# STM32F429VIT6-v1_0_0.net
KiCad netlist of a schematic drawn in EAGLE
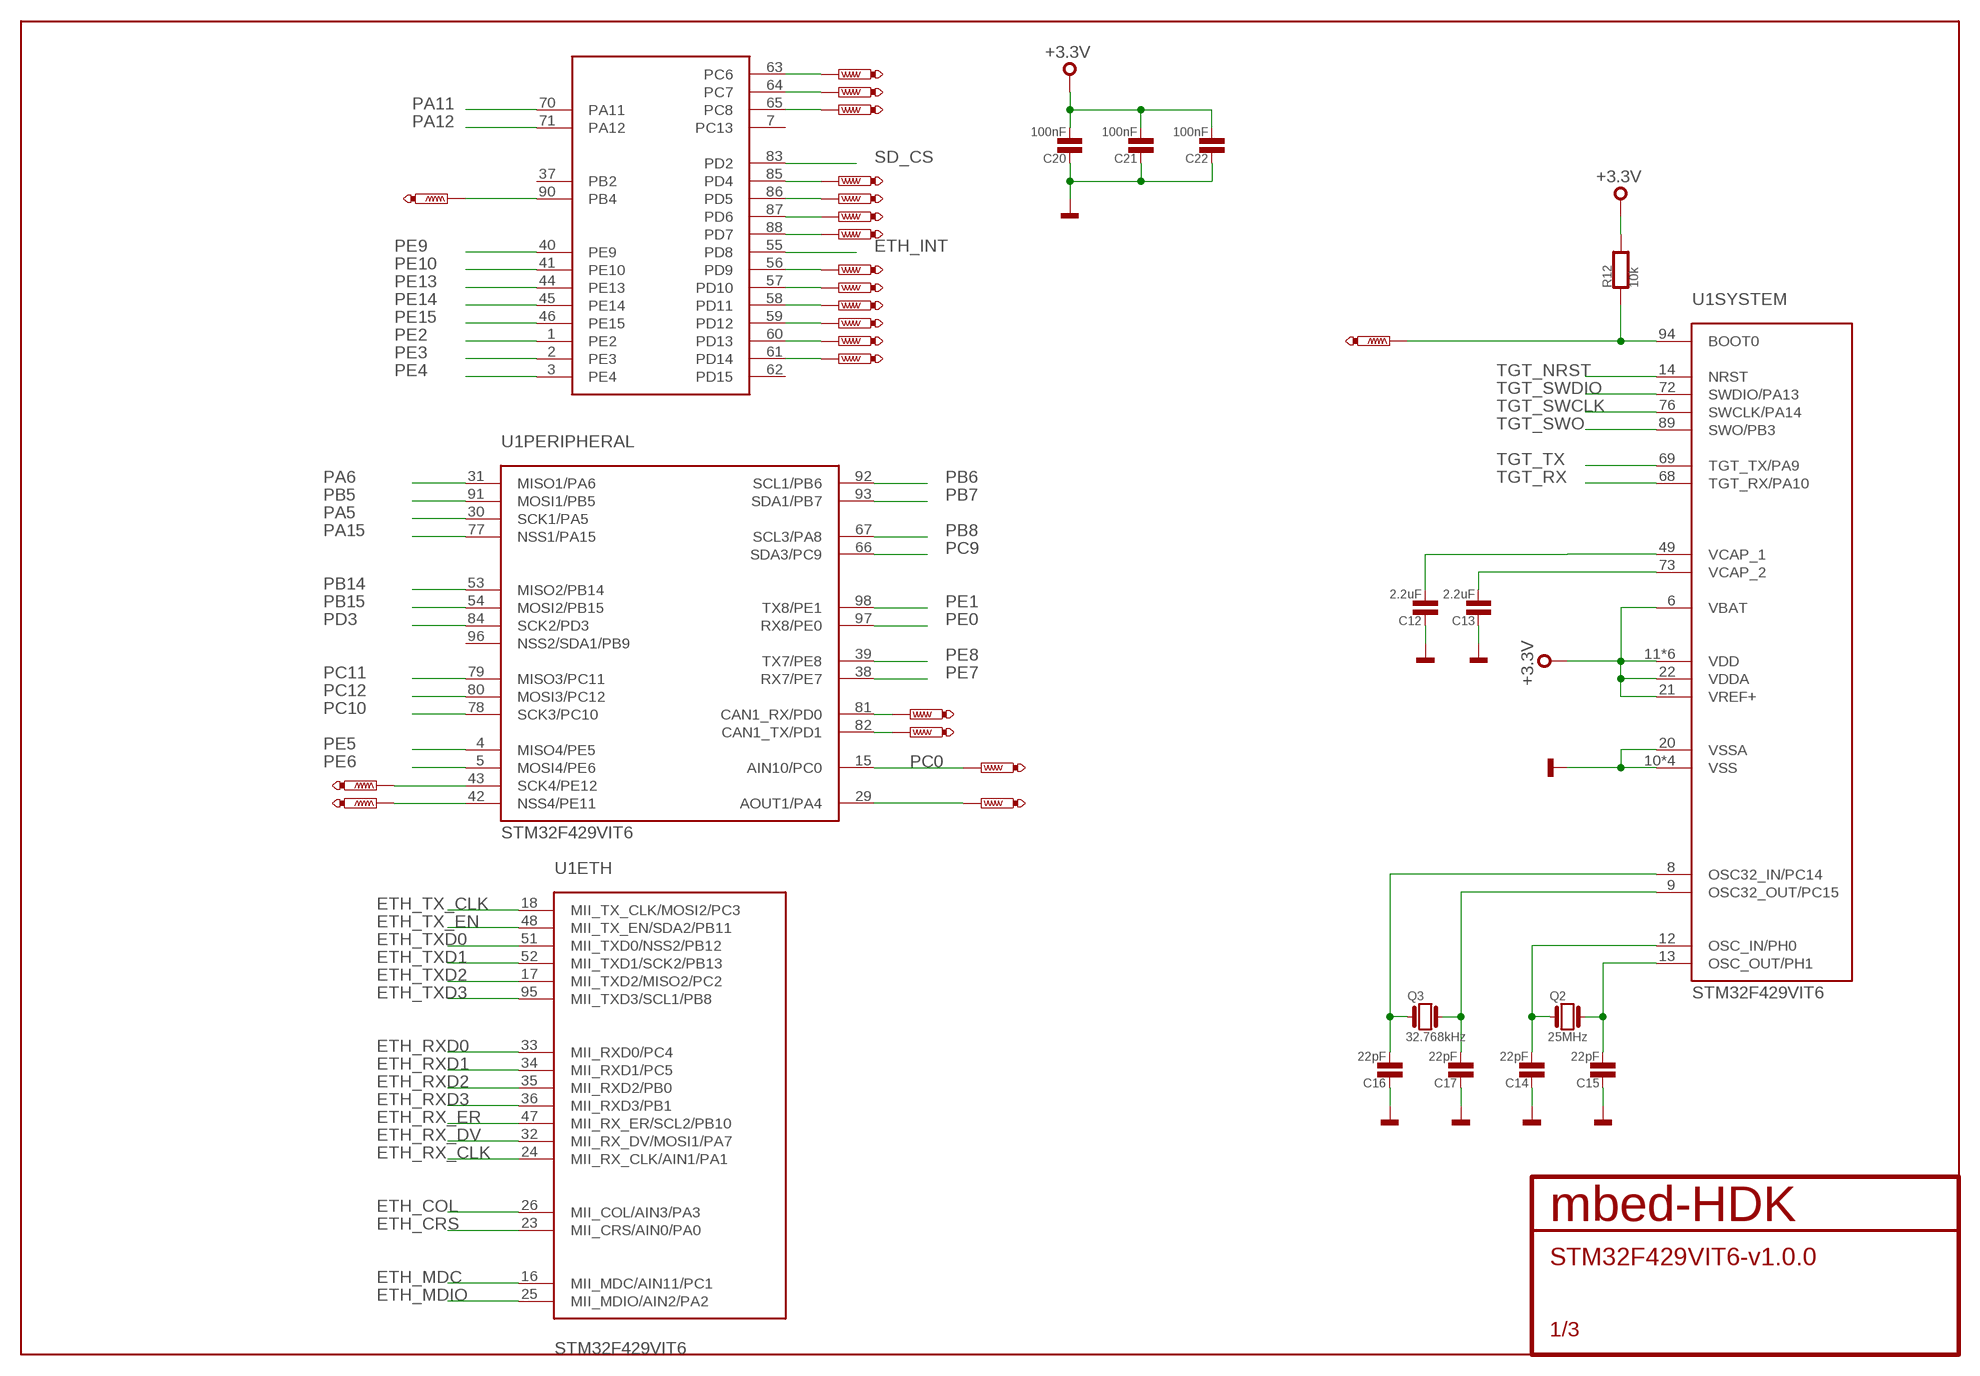
[diagram p0: schematic, sheet 1]
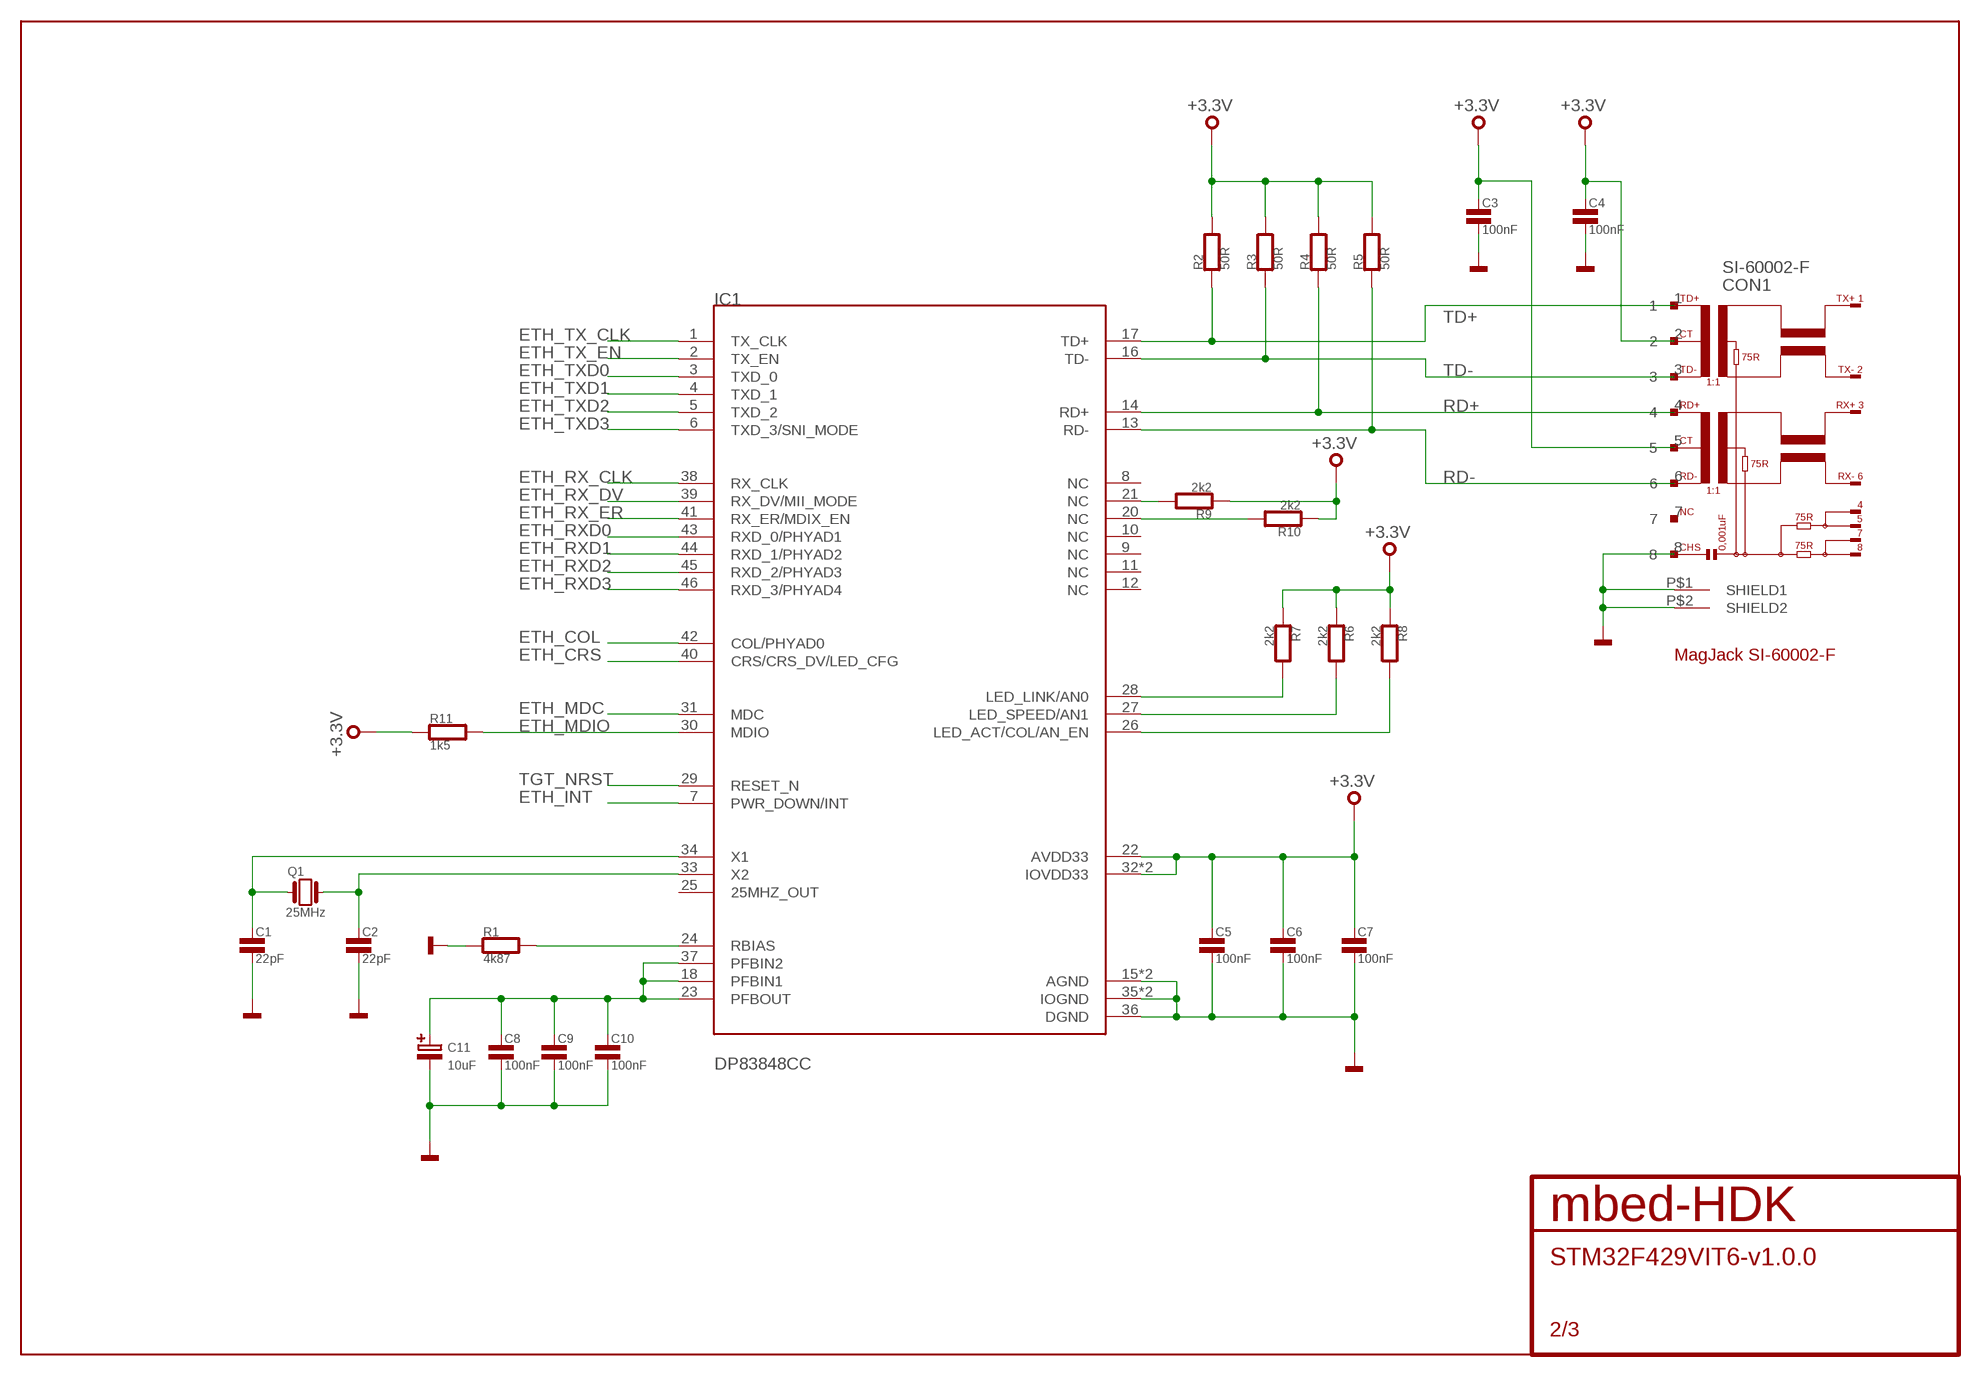
[diagram p1: schematic, sheet 2]
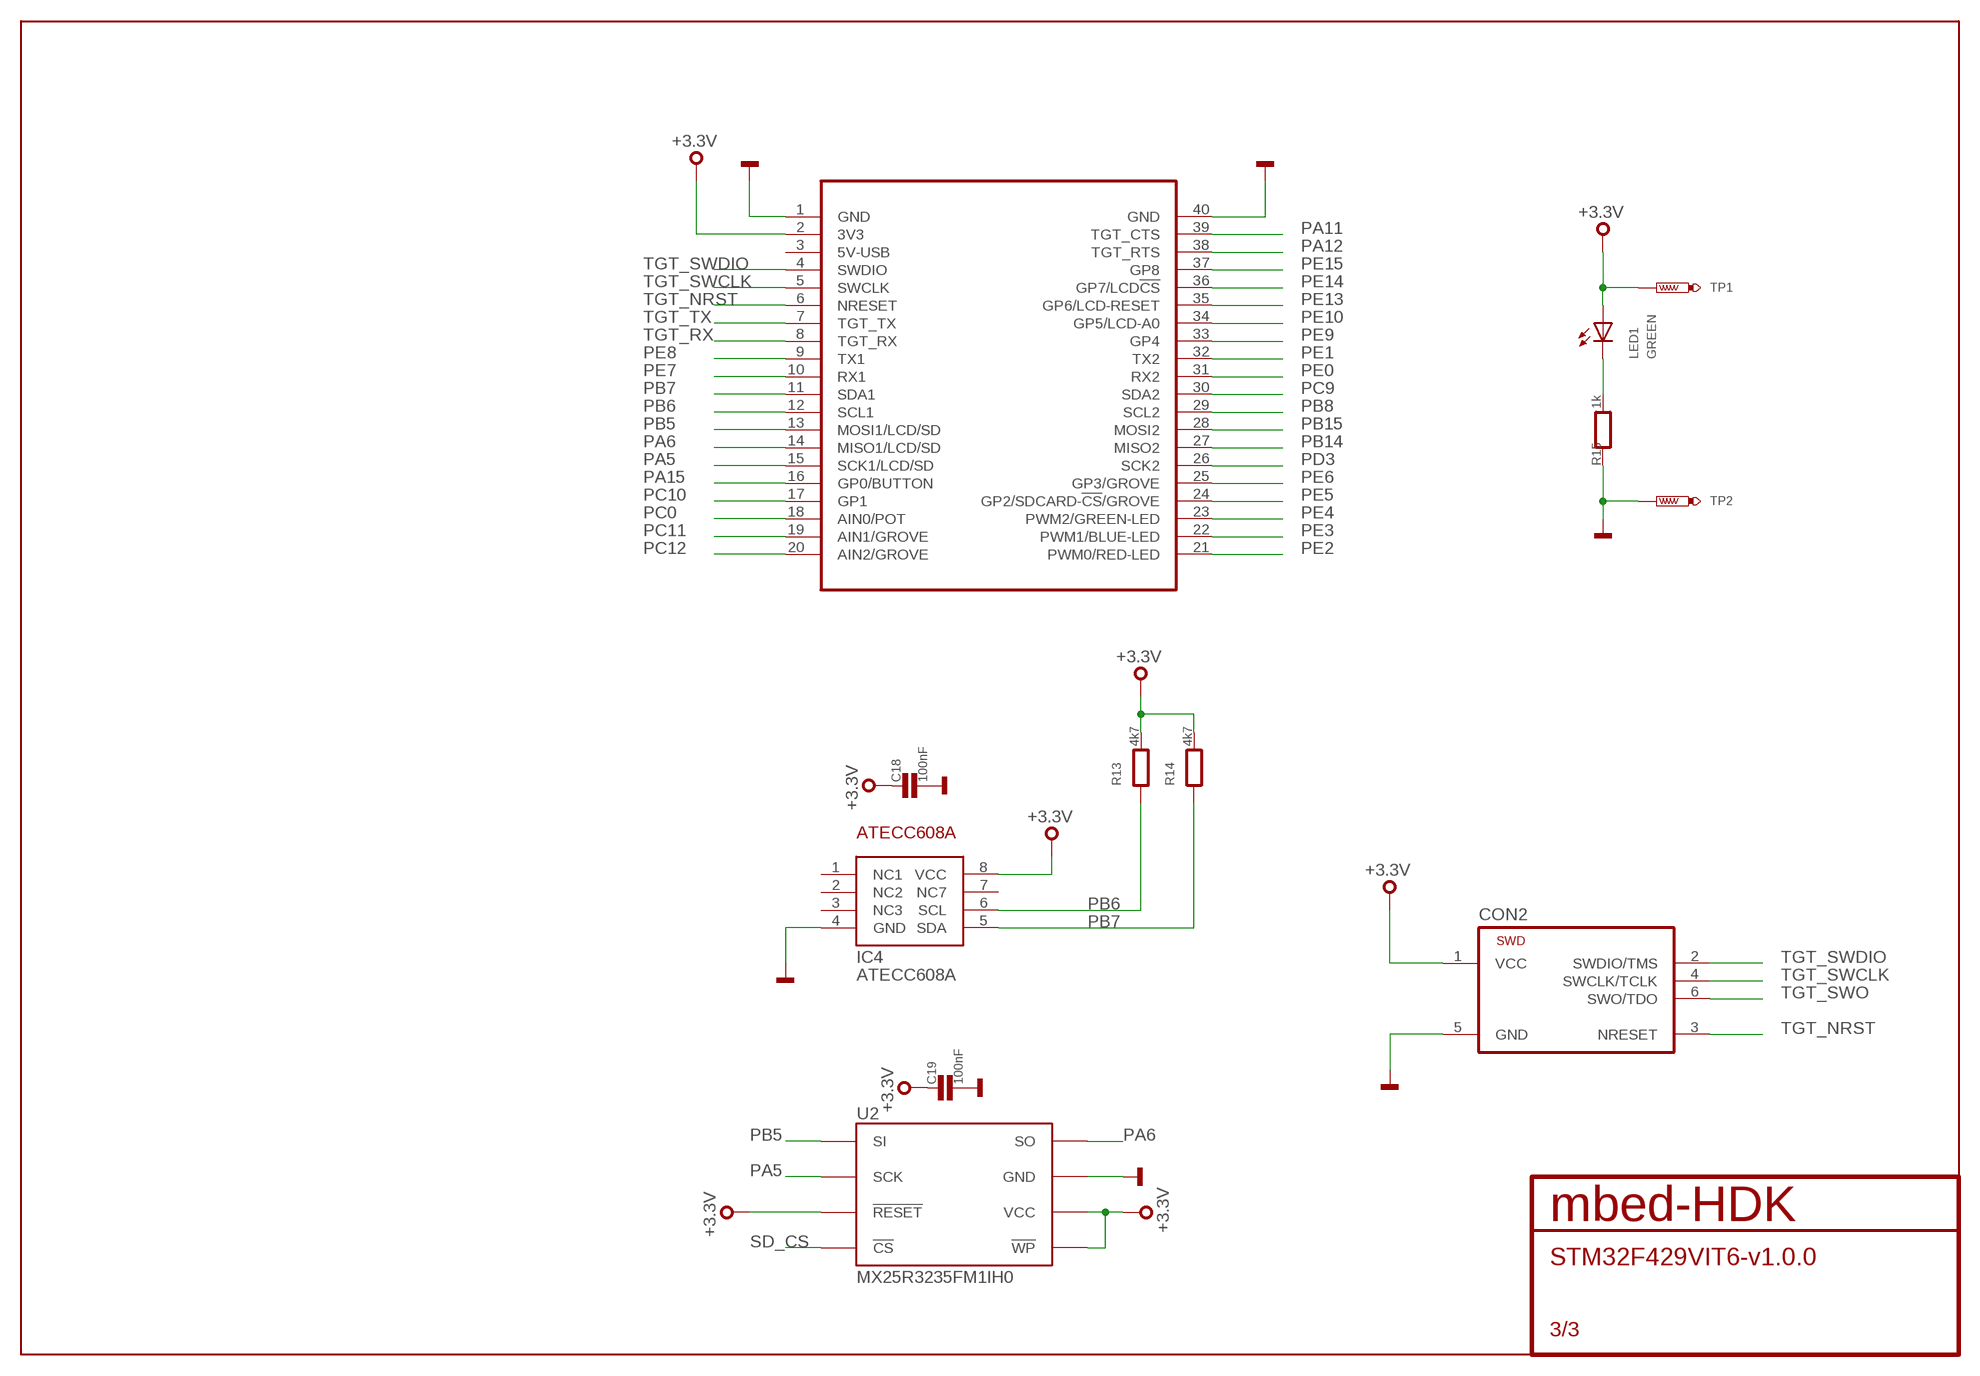
[diagram p2: schematic, sheet 3]

(export (version "E")
  (design (tool "Eeschema 10.0.6"))
  (components
    (comp (ref "C12")
      (value "2.2uF")
      (footprint "eagle-import:0402")
      (libsource (lib "eagle-import") (part "C0402"))
    )
    (comp (ref "C13")
      (value "2.2uF")
      (footprint "eagle-import:0402")
      (libsource (lib "eagle-import") (part "C0402"))
    )
    (comp (ref "C14")
      (value "22pF")
      (footprint "eagle-import:0603")
      (libsource (lib "eagle-import") (part "C0603"))
    )
    (comp (ref "C15")
      (value "22pF")
      (footprint "eagle-import:0603")
      (libsource (lib "eagle-import") (part "C0603"))
    )
    (comp (ref "C16")
      (value "22pF")
      (footprint "eagle-import:0603")
      (libsource (lib "eagle-import") (part "C0603"))
    )
    (comp (ref "C17")
      (value "22pF")
      (footprint "eagle-import:0603")
      (libsource (lib "eagle-import") (part "C0603"))
    )
    (comp (ref "C20")
      (value "100nF")
      (footprint "eagle-import:0402")
      (libsource (lib "eagle-import") (part "C0402"))
    )
    (comp (ref "C21")
      (value "100nF")
      (footprint "eagle-import:0402")
      (libsource (lib "eagle-import") (part "C0402"))
    )
    (comp (ref "C22")
      (value "100nF")
      (footprint "eagle-import:0402")
      (libsource (lib "eagle-import") (part "C0402"))
    )
    (comp (ref "Q2")
      (value "25MHz")
      (footprint "eagle-import:3.2X.2.5")
      (libsource (lib "eagle-import") (part "GENERIC-CRYSTAL_3.2X2.5"))
    )
    (comp (ref "Q3")
      (value "32.768kHz")
      (footprint "eagle-import:FC135")
      (libsource (lib "eagle-import") (part "GENERIC-CRYSTAL_FC135"))
    )
    (comp (ref "R12")
      (value "10k")
      (footprint "eagle-import:0402")
      (libsource (lib "eagle-import") (part "R0402"))
    )
    (comp (ref "TP3")
      (value "PTR1TP06R")
      (footprint "eagle-import:TP06R")
      (libsource (lib "eagle-import") (part "PTR1TP06R"))
    )
    (comp (ref "TP4")
      (value "PTR1TP06R")
      (footprint "eagle-import:TP06R")
      (libsource (lib "eagle-import") (part "PTR1TP06R"))
    )
    (comp (ref "TP5")
      (value "PTR1TP06R")
      (footprint "eagle-import:TP06R")
      (libsource (lib "eagle-import") (part "PTR1TP06R"))
    )
    (comp (ref "TP6")
      (value "PTR1TP06R")
      (footprint "eagle-import:TP06R")
      (libsource (lib "eagle-import") (part "PTR1TP06R"))
    )
    (comp (ref "TP7")
      (value "PTR1TP06R")
      (footprint "eagle-import:TP06R")
      (libsource (lib "eagle-import") (part "PTR1TP06R"))
    )
    (comp (ref "TP8")
      (value "PTR1TP06R")
      (footprint "eagle-import:TP06R")
      (libsource (lib "eagle-import") (part "PTR1TP06R"))
    )
    (comp (ref "TP9")
      (value "PTR1TP06R")
      (footprint "eagle-import:TP06R")
      (libsource (lib "eagle-import") (part "PTR1TP06R"))
    )
    (comp (ref "TP10")
      (value "PTR1TP06R")
      (footprint "eagle-import:TP06R")
      (libsource (lib "eagle-import") (part "PTR1TP06R"))
    )
    (comp (ref "TP11")
      (value "PTR1TP06R")
      (footprint "eagle-import:TP06R")
      (libsource (lib "eagle-import") (part "PTR1TP06R"))
    )
    (comp (ref "TP12")
      (value "PTR1TP06R")
      (footprint "eagle-import:TP06R")
      (libsource (lib "eagle-import") (part "PTR1TP06R"))
    )
    (comp (ref "TP13")
      (value "PTR1TP06R")
      (footprint "eagle-import:TP06R")
      (libsource (lib "eagle-import") (part "PTR1TP06R"))
    )
    (comp (ref "TP15")
      (value "PTR1TP06R")
      (footprint "eagle-import:TP06R")
      (libsource (lib "eagle-import") (part "PTR1TP06R"))
    )
    (comp (ref "TP16")
      (value "PTR1TP06R")
      (footprint "eagle-import:TP06R")
      (libsource (lib "eagle-import") (part "PTR1TP06R"))
    )
    (comp (ref "TP17")
      (value "PTR1TP06R")
      (footprint "eagle-import:TP06R")
      (libsource (lib "eagle-import") (part "PTR1TP06R"))
    )
    (comp (ref "TP18")
      (value "PTR1TP06R")
      (footprint "eagle-import:TP06R")
      (libsource (lib "eagle-import") (part "PTR1TP06R"))
    )
    (comp (ref "TP19")
      (value "PTR1TP06R")
      (footprint "eagle-import:TP06R")
      (libsource (lib "eagle-import") (part "PTR1TP06R"))
    )
    (comp (ref "TP20")
      (value "PTR1TP06R")
      (footprint "eagle-import:TP06R")
      (libsource (lib "eagle-import") (part "PTR1TP06R"))
    )
    (comp (ref "TP21")
      (value "PTR1TP06R")
      (footprint "eagle-import:TP06R")
      (libsource (lib "eagle-import") (part "PTR1TP06R"))
    )
    (comp (ref "TP22")
      (value "PTR1TP06R")
      (footprint "eagle-import:TP06R")
      (libsource (lib "eagle-import") (part "PTR1TP06R"))
    )
    (comp (ref "TP23")
      (value "PTR1TP06R")
      (footprint "eagle-import:TP06R")
      (libsource (lib "eagle-import") (part "PTR1TP06R"))
    )
    (comp (ref "TP24")
      (value "PTR1TP06R")
      (footprint "eagle-import:TP06R")
      (libsource (lib "eagle-import") (part "PTR1TP06R"))
    )
    (comp (ref "U1")
      (value "STM32F429VIT6")
      (footprint "eagle-import:QFP50P1600X1600X160-100N")
      (libsource (lib "eagle-import") (part "STM32F429VIT6"))
    )
    (comp (ref "C18")
      (value "100nF")
      (footprint "eagle-import:0402")
      (libsource (lib "eagle-import") (part "CAPACITOR0402"))
    )
    (comp (ref "C19")
      (value "100nF")
      (footprint "eagle-import:0402")
      (libsource (lib "eagle-import") (part "CAPACITOR0402"))
    )
    (comp (ref "CON2")
      (value "TC2030-CTX-NL")
      (footprint "eagle-import:TC2030-CTX-NL")
      (libsource (lib "eagle-import") (part "TC2030-CTX-NL"))
    )
    (comp (ref "IC4")
      (value "ATECC608A")
      (footprint "eagle-import:SO8")
      (libsource (lib "eagle-import") (part "ATECC608A"))
    )
    (comp (ref "LED1")
      (value "GREEN")
      (footprint "eagle-import:CHIPLED_0603")
      (fields (field (name "MF") "Wurth Electronics Inc"))
      (libsource (lib "eagle-import") (part "SMD_LED0603"))
    )
    (comp (ref "MOD1")
      (value "MODULE_DAUGHTER")
      (footprint "eagle-import:MODULE_DAUGHTER")
      (libsource (lib "eagle-import") (part "MODULE_DAUGHTER"))
    )
    (comp (ref "R13")
      (value "4k7")
      (footprint "eagle-import:0402")
      (libsource (lib "eagle-import") (part "RESISTOR0402"))
    )
    (comp (ref "R14")
      (value "4k7")
      (footprint "eagle-import:0402")
      (libsource (lib "eagle-import") (part "RESISTOR0402"))
    )
    (comp (ref "R15")
      (value "1k")
      (footprint "eagle-import:0603")
      (libsource (lib "eagle-import") (part "RESISTOR0603"))
    )
    (comp (ref "TP1")
      (value "TEST-POINT-50R-PTH")
      (footprint "eagle-import:TP50-PTH")
      (libsource (lib "eagle-import") (part "TEST-POINT-50R-PTH"))
    )
    (comp (ref "TP2")
      (value "TEST-POINT-50R-PTH")
      (footprint "eagle-import:TP50-PTH")
      (libsource (lib "eagle-import") (part "TEST-POINT-50R-PTH"))
    )
    (comp (ref "U2")
      (value "MX25R3235FM1IH0")
      (footprint "eagle-import:SO8")
      (fields (field (name "MF") "Macronix"))
      (libsource (lib "eagle-import") (part "MX25R3235FM1IH0"))
    )
    (comp (ref "C1")
      (value "22pF")
      (footprint "eagle-import:0402")
      (libsource (lib "eagle-import") (part "C0402"))
    )
    (comp (ref "C2")
      (value "22pF")
      (footprint "eagle-import:0402")
      (libsource (lib "eagle-import") (part "C0402"))
    )
    (comp (ref "C3")
      (value "100nF")
      (footprint "eagle-import:0402")
      (libsource (lib "eagle-import") (part "C0402"))
    )
    (comp (ref "C4")
      (value "100nF")
      (footprint "eagle-import:0402")
      (libsource (lib "eagle-import") (part "C0402"))
    )
    (comp (ref "C5")
      (value "100nF")
      (footprint "eagle-import:0402")
      (libsource (lib "eagle-import") (part "C0402"))
    )
    (comp (ref "C6")
      (value "100nF")
      (footprint "eagle-import:0402")
      (libsource (lib "eagle-import") (part "C0402"))
    )
    (comp (ref "C7")
      (value "100nF")
      (footprint "eagle-import:0402")
      (libsource (lib "eagle-import") (part "C0402"))
    )
    (comp (ref "C8")
      (value "100nF")
      (footprint "eagle-import:0402")
      (libsource (lib "eagle-import") (part "C0402"))
    )
    (comp (ref "C9")
      (value "100nF")
      (footprint "eagle-import:0402")
      (libsource (lib "eagle-import") (part "C0402"))
    )
    (comp (ref "C10")
      (value "100nF")
      (footprint "eagle-import:0402")
      (libsource (lib "eagle-import") (part "C0402"))
    )
    (comp (ref "C11")
      (value "10uF")
      (footprint "eagle-import:SMC_A")
      (libsource (lib "eagle-import") (part "C-POLA"))
    )
    (comp (ref "CON1")
      (value "SI-60002-F")
      (footprint "eagle-import:RJ45")
      (fields (field (name "MF") "Stewart Connector"))
      (libsource (lib "eagle-import") (part "SI-60002-F"))
    )
    (comp (ref "IC1")
      (value "DP83848CC")
      (footprint "eagle-import:LQFP-48")
      (libsource (lib "eagle-import") (part "DP83848CC"))
    )
    (comp (ref "Q1")
      (value "25MHz")
      (footprint "eagle-import:3.2X.2.5")
      (libsource (lib "eagle-import") (part "GENERIC-CRYSTAL_3.2X2.5"))
    )
    (comp (ref "R1")
      (value "4k87")
      (footprint "eagle-import:0402")
      (libsource (lib "eagle-import") (part "R0402"))
    )
    (comp (ref "R2")
      (value "50R")
      (footprint "eagle-import:0402")
      (libsource (lib "eagle-import") (part "R0402"))
    )
    (comp (ref "R3")
      (value "50R")
      (footprint "eagle-import:0402")
      (libsource (lib "eagle-import") (part "R0402"))
    )
    (comp (ref "R4")
      (value "50R")
      (footprint "eagle-import:0402")
      (libsource (lib "eagle-import") (part "R0402"))
    )
    (comp (ref "R5")
      (value "50R")
      (footprint "eagle-import:0402")
      (libsource (lib "eagle-import") (part "R0402"))
    )
    (comp (ref "R6")
      (value "2k2")
      (footprint "eagle-import:0402")
      (libsource (lib "eagle-import") (part "R0402"))
    )
    (comp (ref "R7")
      (value "2k2")
      (footprint "eagle-import:0402")
      (libsource (lib "eagle-import") (part "R0402"))
    )
    (comp (ref "R8")
      (value "2k2")
      (footprint "eagle-import:0402")
      (libsource (lib "eagle-import") (part "R0402"))
    )
    (comp (ref "R9")
      (value "2k2")
      (footprint "eagle-import:0402")
      (libsource (lib "eagle-import") (part "R0402"))
    )
    (comp (ref "R10")
      (value "2k2")
      (footprint "eagle-import:0402")
      (libsource (lib "eagle-import") (part "R0402"))
    )
    (comp (ref "R11")
      (value "1k5")
      (footprint "eagle-import:0402")
      (libsource (lib "eagle-import") (part "R0402"))
    )
  )
  (nets
    (net (code "1") (name "+3.3V") (class "Default")
      (node (ref "C18") (pin "1") (pinfunction "P$1_1") (pintype "passive"))
      (node (ref "C19") (pin "1") (pinfunction "P$1_1") (pintype "passive"))
      (node (ref "C20") (pin "2") (pinfunction "P$2_2") (pintype "passive"))
      (node (ref "C21") (pin "2") (pinfunction "P$2_2") (pintype "passive"))
      (node (ref "C22") (pin "2") (pinfunction "P$2_2") (pintype "passive"))
      (node (ref "C3") (pin "1") (pinfunction "P$1_1") (pintype "passive"))
      (node (ref "C4") (pin "1") (pinfunction "P$1_1") (pintype "passive"))
      (node (ref "C5") (pin "1") (pinfunction "P$1_1") (pintype "passive"))
      (node (ref "C6") (pin "1") (pinfunction "P$1_1") (pintype "passive"))
      (node (ref "C7") (pin "1") (pinfunction "P$1_1") (pintype "passive"))
      (node (ref "CON1") (pin "2") (pinfunction "2_2") (pintype "passive"))
      (node (ref "CON1") (pin "5") (pinfunction "5_5") (pintype "passive"))
      (node (ref "CON2") (pin "1") (pinfunction "VCC_1") (pintype "passive"))
      (node (ref "IC1") (pin "22") (pinfunction "AVDD33_22") (pintype "bidirectional"))
      (node (ref "IC1") (pin "32") (pinfunction "IOVDD33_32") (pintype "bidirectional"))
      (node (ref "IC1") (pin "48") (pinfunction "IOVDD33_48") (pintype "bidirectional"))
      (node (ref "IC4") (pin "8") (pinfunction "VCC_8") (pintype "bidirectional"))
      (node (ref "LED1") (pin "A") (pinfunction "A_A") (pintype "passive"))
      (node (ref "MOD1") (pin "2") (pinfunction "3V3_2") (pintype "bidirectional"))
      (node (ref "R10") (pin "1") (pinfunction "P$1_1") (pintype "passive"))
      (node (ref "R11") (pin "1") (pinfunction "P$1_1") (pintype "passive"))
      (node (ref "R12") (pin "2") (pinfunction "P$2_2") (pintype "passive"))
      (node (ref "R13") (pin "2") (pinfunction "P$2_2") (pintype "passive"))
      (node (ref "R14") (pin "2") (pinfunction "P$2_2") (pintype "passive"))
      (node (ref "R2") (pin "2") (pinfunction "P$2_2") (pintype "passive"))
      (node (ref "R3") (pin "2") (pinfunction "P$2_2") (pintype "passive"))
      (node (ref "R4") (pin "2") (pinfunction "P$2_2") (pintype "passive"))
      (node (ref "R5") (pin "2") (pinfunction "P$2_2") (pintype "passive"))
      (node (ref "R6") (pin "1") (pinfunction "P$1_1") (pintype "passive"))
      (node (ref "R7") (pin "1") (pinfunction "P$1_1") (pintype "passive"))
      (node (ref "R8") (pin "1") (pinfunction "P$1_1") (pintype "passive"))
      (node (ref "R9") (pin "1") (pinfunction "P$1_1") (pintype "passive"))
      (node (ref "TP1") (pin "TP") (pinfunction "TP_TP") (pintype "input"))
      (node (ref "U1") (pin "100") (pinfunction "VDD_100") (pintype "power_in"))
      (node (ref "U1") (pin "11") (pinfunction "VDD_11") (pintype "power_in"))
      (node (ref "U1") (pin "19") (pinfunction "VDD_19") (pintype "power_in"))
      (node (ref "U1") (pin "21") (pinfunction "VREF+_21") (pintype "power_in"))
      (node (ref "U1") (pin "22") (pinfunction "VDDA_22") (pintype "power_in"))
      (node (ref "U1") (pin "28") (pinfunction "VDD_28") (pintype "power_in"))
      (node (ref "U1") (pin "50") (pinfunction "VDD_50") (pintype "power_in"))
      (node (ref "U1") (pin "6") (pinfunction "VBAT_6") (pintype "power_in"))
      (node (ref "U1") (pin "75") (pinfunction "VDD_75") (pintype "power_in"))
      (node (ref "U2") (pin "3") (pinfunction "~{WP}_3") (pintype "bidirectional"))
      (node (ref "U2") (pin "7") (pinfunction "~{RESET}_7") (pintype "bidirectional"))
      (node (ref "U2") (pin "8") (pinfunction "VCC_8") (pintype "bidirectional"))
    )
    (net (code "2") (name "ETH_COL") (class "Default")
      (node (ref "IC1") (pin "42") (pinfunction "COL/PHYAD0_42") (pintype "bidirectional"))
      (node (ref "U1") (pin "26") (pinfunction "MII_COL/AIN3/PA3_26") (pintype "bidirectional"))
    )
    (net (code "3") (name "ETH_CRS") (class "Default")
      (node (ref "IC1") (pin "40") (pinfunction "CRS/CRS_DV/LED_CFG_40") (pintype "bidirectional"))
      (node (ref "U1") (pin "23") (pinfunction "MII_CRS/AIN0/PA0_23") (pintype "bidirectional"))
    )
    (net (code "4") (name "ETH_INT") (class "Default")
      (node (ref "IC1") (pin "7") (pinfunction "PWR_DOWN/INT_7") (pintype "bidirectional"))
      (node (ref "U1") (pin "55") (pinfunction "PD8_55") (pintype "bidirectional"))
    )
    (net (code "5") (name "ETH_MDC") (class "Default")
      (node (ref "IC1") (pin "31") (pinfunction "MDC_31") (pintype "bidirectional"))
      (node (ref "U1") (pin "16") (pinfunction "MII_MDC/AIN11/PC1_16") (pintype "bidirectional"))
    )
    (net (code "6") (name "ETH_MDIO") (class "Default")
      (node (ref "IC1") (pin "30") (pinfunction "MDIO_30") (pintype "bidirectional"))
      (node (ref "R11") (pin "2") (pinfunction "P$2_2") (pintype "passive"))
      (node (ref "U1") (pin "25") (pinfunction "MII_MDIO/AIN2/PA2_25") (pintype "bidirectional"))
    )
    (net (code "7") (name "ETH_RXD0") (class "Default")
      (node (ref "IC1") (pin "43") (pinfunction "RXD_0/PHYAD1_43") (pintype "bidirectional"))
      (node (ref "U1") (pin "33") (pinfunction "MII_RXD0/PC4_33") (pintype "bidirectional"))
    )
    (net (code "8") (name "ETH_RXD1") (class "Default")
      (node (ref "IC1") (pin "44") (pinfunction "RXD_1/PHYAD2_44") (pintype "bidirectional"))
      (node (ref "U1") (pin "34") (pinfunction "MII_RXD1/PC5_34") (pintype "bidirectional"))
    )
    (net (code "9") (name "ETH_RXD2") (class "Default")
      (node (ref "IC1") (pin "45") (pinfunction "RXD_2/PHYAD3_45") (pintype "bidirectional"))
      (node (ref "U1") (pin "35") (pinfunction "MII_RXD2/PB0_35") (pintype "bidirectional"))
    )
    (net (code "10") (name "ETH_RXD3") (class "Default")
      (node (ref "IC1") (pin "46") (pinfunction "RXD_3/PHYAD4_46") (pintype "bidirectional"))
      (node (ref "U1") (pin "36") (pinfunction "MII_RXD3/PB1_36") (pintype "bidirectional"))
    )
    (net (code "11") (name "ETH_RX_CLK") (class "Default")
      (node (ref "IC1") (pin "38") (pinfunction "RX_CLK_38") (pintype "bidirectional"))
      (node (ref "U1") (pin "24") (pinfunction "MII_RX_CLK/AIN1/PA1_24") (pintype "bidirectional"))
    )
    (net (code "12") (name "ETH_RX_DV") (class "Default")
      (node (ref "IC1") (pin "39") (pinfunction "RX_DV/MII_MODE_39") (pintype "bidirectional"))
      (node (ref "U1") (pin "32") (pinfunction "MII_RX_DV/MOSI1/PA7_32") (pintype "bidirectional"))
    )
    (net (code "13") (name "ETH_RX_ER") (class "Default")
      (node (ref "IC1") (pin "41") (pinfunction "RX_ER/MDIX_EN_41") (pintype "bidirectional"))
      (node (ref "U1") (pin "47") (pinfunction "MII_RX_ER/SCL2/PB10_47") (pintype "bidirectional"))
    )
    (net (code "14") (name "ETH_TXD0") (class "Default")
      (node (ref "IC1") (pin "3") (pinfunction "TXD_0_3") (pintype "bidirectional"))
      (node (ref "U1") (pin "51") (pinfunction "MII_TXD0/NSS2/PB12_51") (pintype "bidirectional"))
    )
    (net (code "15") (name "ETH_TXD1") (class "Default")
      (node (ref "IC1") (pin "4") (pinfunction "TXD_1_4") (pintype "bidirectional"))
      (node (ref "U1") (pin "52") (pinfunction "MII_TXD1/SCK2/PB13_52") (pintype "bidirectional"))
    )
    (net (code "16") (name "ETH_TXD2") (class "Default")
      (node (ref "IC1") (pin "5") (pinfunction "TXD_2_5") (pintype "bidirectional"))
      (node (ref "U1") (pin "17") (pinfunction "MII_TXD2/MISO2/PC2_17") (pintype "bidirectional"))
    )
    (net (code "17") (name "ETH_TXD3") (class "Default")
      (node (ref "IC1") (pin "6") (pinfunction "TXD_3/SNI_MODE_6") (pintype "bidirectional"))
      (node (ref "U1") (pin "95") (pinfunction "MII_TXD3/SCL1/PB8_95") (pintype "bidirectional"))
    )
    (net (code "18") (name "ETH_TX_CLK") (class "Default")
      (node (ref "IC1") (pin "1") (pinfunction "TX_CLK_1") (pintype "bidirectional"))
      (node (ref "U1") (pin "18") (pinfunction "MII_TX_CLK/MOSI2/PC3_18") (pintype "bidirectional"))
    )
    (net (code "19") (name "ETH_TX_EN") (class "Default")
      (node (ref "IC1") (pin "2") (pinfunction "TX_EN_2") (pintype "bidirectional"))
      (node (ref "U1") (pin "48") (pinfunction "MII_TX_EN/SDA2/PB11_48") (pintype "bidirectional"))
    )
    (net (code "20") (name "GND") (class "Default")
      (node (ref "C1") (pin "2") (pinfunction "P$2_2") (pintype "passive"))
      (node (ref "C10") (pin "2") (pinfunction "P$2_2") (pintype "passive"))
      (node (ref "C11") (pin "-") (pinfunction "-_-") (pintype "passive"))
      (node (ref "C12") (pin "1") (pinfunction "P$1_1") (pintype "passive"))
      (node (ref "C13") (pin "1") (pinfunction "P$1_1") (pintype "passive"))
      (node (ref "C14") (pin "1") (pinfunction "P$1_1") (pintype "passive"))
      (node (ref "C15") (pin "1") (pinfunction "P$1_1") (pintype "passive"))
      (node (ref "C16") (pin "1") (pinfunction "P$1_1") (pintype "passive"))
      (node (ref "C17") (pin "1") (pinfunction "P$1_1") (pintype "passive"))
      (node (ref "C18") (pin "2") (pinfunction "P$2_2") (pintype "passive"))
      (node (ref "C19") (pin "2") (pinfunction "P$2_2") (pintype "passive"))
      (node (ref "C2") (pin "2") (pinfunction "P$2_2") (pintype "passive"))
      (node (ref "C20") (pin "1") (pinfunction "P$1_1") (pintype "passive"))
      (node (ref "C21") (pin "1") (pinfunction "P$1_1") (pintype "passive"))
      (node (ref "C22") (pin "1") (pinfunction "P$1_1") (pintype "passive"))
      (node (ref "C3") (pin "2") (pinfunction "P$2_2") (pintype "passive"))
      (node (ref "C4") (pin "2") (pinfunction "P$2_2") (pintype "passive"))
      (node (ref "C5") (pin "2") (pinfunction "P$2_2") (pintype "passive"))
      (node (ref "C6") (pin "2") (pinfunction "P$2_2") (pintype "passive"))
      (node (ref "C7") (pin "2") (pinfunction "P$2_2") (pintype "passive"))
      (node (ref "C8") (pin "2") (pinfunction "P$2_2") (pintype "passive"))
      (node (ref "C9") (pin "2") (pinfunction "P$2_2") (pintype "passive"))
      (node (ref "CON1") (pin "8") (pinfunction "8_8") (pintype "passive"))
      (node (ref "CON1") (pin "P$1") (pinfunction "SHIELD1_P$1") (pintype "bidirectional"))
      (node (ref "CON1") (pin "P$2") (pinfunction "SHIELD2_P$2") (pintype "bidirectional"))
      (node (ref "CON2") (pin "5") (pinfunction "GND_5") (pintype "passive"))
      (node (ref "IC1") (pin "15") (pinfunction "AGND_15") (pintype "bidirectional"))
      (node (ref "IC1") (pin "19") (pinfunction "AGND_19") (pintype "bidirectional"))
      (node (ref "IC1") (pin "35") (pinfunction "IOGND_35") (pintype "bidirectional"))
      (node (ref "IC1") (pin "36") (pinfunction "DGND_36") (pintype "bidirectional"))
      (node (ref "IC1") (pin "47") (pinfunction "IOGND_47") (pintype "bidirectional"))
      (node (ref "IC4") (pin "4") (pinfunction "GND_4") (pintype "bidirectional"))
      (node (ref "MOD1") (pin "1") (pinfunction "GND_1") (pintype "bidirectional"))
      (node (ref "MOD1") (pin "40") (pinfunction "GND_40") (pintype "bidirectional"))
      (node (ref "R1") (pin "1") (pinfunction "P$1_1") (pintype "passive"))
      (node (ref "R15") (pin "1") (pinfunction "P$1_1") (pintype "passive"))
      (node (ref "TP2") (pin "TP") (pinfunction "TP_TP") (pintype "input"))
      (node (ref "U1") (pin "10") (pinfunction "VSS_10") (pintype "power_in"))
      (node (ref "U1") (pin "20") (pinfunction "VSSA_20") (pintype "power_in"))
      (node (ref "U1") (pin "27") (pinfunction "VSS_27") (pintype "power_in"))
      (node (ref "U1") (pin "74") (pinfunction "VSS_74") (pintype "power_in"))
      (node (ref "U1") (pin "99") (pinfunction "VSS_99") (pintype "power_in"))
      (node (ref "U2") (pin "4") (pinfunction "GND_4") (pintype "bidirectional"))
    )
    (net (code "21") (name "Net-(C1-P$1)") (class "Default")
      (node (ref "C1") (pin "1") (pinfunction "P$1_1") (pintype "passive"))
      (node (ref "IC1") (pin "34") (pinfunction "X1_34") (pintype "bidirectional"))
      (node (ref "Q1") (pin "P$1") (pinfunction "1_P$1") (pintype "passive"))
    )
    (net (code "22") (name "Net-(C2-P$1)") (class "Default")
      (node (ref "C2") (pin "1") (pinfunction "P$1_1") (pintype "passive"))
      (node (ref "IC1") (pin "33") (pinfunction "X2_33") (pintype "bidirectional"))
      (node (ref "Q1") (pin "P$3") (pinfunction "2_P$3") (pintype "passive"))
    )
    (net (code "23") (name "Net-(C10-P$1)") (class "Default")
      (node (ref "C10") (pin "1") (pinfunction "P$1_1") (pintype "passive"))
      (node (ref "C11") (pin "+") (pinfunction "+_+") (pintype "passive"))
      (node (ref "C8") (pin "1") (pinfunction "P$1_1") (pintype "passive"))
      (node (ref "C9") (pin "1") (pinfunction "P$1_1") (pintype "passive"))
      (node (ref "IC1") (pin "18") (pinfunction "PFBIN1_18") (pintype "bidirectional"))
      (node (ref "IC1") (pin "23") (pinfunction "PFBOUT_23") (pintype "bidirectional"))
      (node (ref "IC1") (pin "37") (pinfunction "PFBIN2_37") (pintype "bidirectional"))
    )
    (net (code "24") (name "Net-(C12-P$2)") (class "Default")
      (node (ref "C12") (pin "2") (pinfunction "P$2_2") (pintype "passive"))
      (node (ref "U1") (pin "49") (pinfunction "VCAP_1_49") (pintype "power_in"))
    )
    (net (code "25") (name "Net-(C13-P$2)") (class "Default")
      (node (ref "C13") (pin "2") (pinfunction "P$2_2") (pintype "passive"))
      (node (ref "U1") (pin "73") (pinfunction "VCAP_2_73") (pintype "power_in"))
    )
    (net (code "26") (name "Net-(C14-P$2)") (class "Default")
      (node (ref "C14") (pin "2") (pinfunction "P$2_2") (pintype "passive"))
      (node (ref "Q2") (pin "P$1") (pinfunction "1_P$1") (pintype "passive"))
      (node (ref "U1") (pin "12") (pinfunction "OSC_IN/PH0_12") (pintype "bidirectional"))
    )
    (net (code "27") (name "Net-(C15-P$2)") (class "Default")
      (node (ref "C15") (pin "2") (pinfunction "P$2_2") (pintype "passive"))
      (node (ref "Q2") (pin "P$3") (pinfunction "2_P$3") (pintype "passive"))
      (node (ref "U1") (pin "13") (pinfunction "OSC_OUT/PH1_13") (pintype "bidirectional"))
    )
    (net (code "28") (name "Net-(C16-P$2)") (class "Default")
      (node (ref "C16") (pin "2") (pinfunction "P$2_2") (pintype "passive"))
      (node (ref "Q3") (pin "X1") (pinfunction "1_X1") (pintype "passive"))
      (node (ref "U1") (pin "8") (pinfunction "OSC32_IN/PC14_8") (pintype "bidirectional"))
    )
    (net (code "29") (name "Net-(C17-P$2)") (class "Default")
      (node (ref "C17") (pin "2") (pinfunction "P$2_2") (pintype "passive"))
      (node (ref "Q3") (pin "X2") (pinfunction "2_X2") (pintype "passive"))
      (node (ref "U1") (pin "9") (pinfunction "OSC32_OUT/PC15_9") (pintype "bidirectional"))
    )
    (net (code "30") (name "Net-(IC1-LED_ACT{slash}COL{slash}AN_EN)") (class "Default")
      (node (ref "IC1") (pin "26") (pinfunction "LED_ACT/COL/AN_EN_26") (pintype "bidirectional"))
      (node (ref "R8") (pin "2") (pinfunction "P$2_2") (pintype "passive"))
    )
    (net (code "31") (name "Net-(IC1-LED_LINK{slash}AN0)") (class "Default")
      (node (ref "IC1") (pin "28") (pinfunction "LED_LINK/AN0_28") (pintype "bidirectional"))
      (node (ref "R7") (pin "2") (pinfunction "P$2_2") (pintype "passive"))
    )
    (net (code "32") (name "Net-(IC1-LED_SPEED{slash}AN1)") (class "Default")
      (node (ref "IC1") (pin "27") (pinfunction "LED_SPEED/AN1_27") (pintype "bidirectional"))
      (node (ref "R6") (pin "2") (pinfunction "P$2_2") (pintype "passive"))
    )
    (net (code "33") (name "Net-(IC1-RBIAS)") (class "Default")
      (node (ref "IC1") (pin "24") (pinfunction "RBIAS_24") (pintype "bidirectional"))
      (node (ref "R1") (pin "2") (pinfunction "P$2_2") (pintype "passive"))
    )
    (net (code "34") (name "Net-(R9-P$2)") (class "Default")
      (node (ref "IC1") (pin "21") (pinfunction "NC_21") (pintype "bidirectional"))
      (node (ref "R9") (pin "2") (pinfunction "P$2_2") (pintype "passive"))
    )
    (net (code "35") (name "Net-(R10-P$2)") (class "Default")
      (node (ref "IC1") (pin "20") (pinfunction "NC_20") (pintype "bidirectional"))
      (node (ref "R10") (pin "2") (pinfunction "P$2_2") (pintype "passive"))
    )
    (net (code "36") (name "Net-(R12-P$1)") (class "Default")
      (node (ref "R12") (pin "1") (pinfunction "P$1_1") (pintype "passive"))
      (node (ref "TP6") (pin "TP") (pinfunction "TP_TP") (pintype "input"))
      (node (ref "U1") (pin "94") (pinfunction "BOOT0_94") (pintype "input"))
    )
    (net (code "37") (name "Net-(R15-P$2)") (class "Default")
      (node (ref "LED1") (pin "C") (pinfunction "C_C") (pintype "passive"))
      (node (ref "R15") (pin "2") (pinfunction "P$2_2") (pintype "passive"))
    )
    (net (code "38") (name "Net-(U1B-PB4)") (class "Default")
      (node (ref "TP11") (pin "TP") (pinfunction "TP_TP") (pintype "input"))
      (node (ref "U1") (pin "90") (pinfunction "PB4_90") (pintype "bidirectional"))
    )
    (net (code "39") (name "Net-(U1B-PC6)") (class "Default")
      (node (ref "TP15") (pin "TP") (pinfunction "TP_TP") (pintype "input"))
      (node (ref "U1") (pin "63") (pinfunction "PC6_63") (pintype "bidirectional"))
    )
    (net (code "40") (name "Net-(U1B-PC7)") (class "Default")
      (node (ref "TP16") (pin "TP") (pinfunction "TP_TP") (pintype "input"))
      (node (ref "U1") (pin "64") (pinfunction "PC7_64") (pintype "bidirectional"))
    )
    (net (code "41") (name "Net-(U1B-PC8)") (class "Default")
      (node (ref "TP17") (pin "TP") (pinfunction "TP_TP") (pintype "input"))
      (node (ref "U1") (pin "65") (pinfunction "PC8_65") (pintype "bidirectional"))
    )
    (net (code "42") (name "Net-(U1B-PD4)") (class "Default")
      (node (ref "TP21") (pin "TP") (pinfunction "TP_TP") (pintype "input"))
      (node (ref "U1") (pin "85") (pinfunction "PD4_85") (pintype "bidirectional"))
    )
    (net (code "43") (name "Net-(U1B-PD5)") (class "Default")
      (node (ref "TP20") (pin "TP") (pinfunction "TP_TP") (pintype "input"))
      (node (ref "U1") (pin "86") (pinfunction "PD5_86") (pintype "bidirectional"))
    )
    (net (code "44") (name "Net-(U1B-PD6)") (class "Default")
      (node (ref "TP19") (pin "TP") (pinfunction "TP_TP") (pintype "input"))
      (node (ref "U1") (pin "87") (pinfunction "PD6_87") (pintype "bidirectional"))
    )
    (net (code "45") (name "Net-(U1B-PD7)") (class "Default")
      (node (ref "TP18") (pin "TP") (pinfunction "TP_TP") (pintype "input"))
      (node (ref "U1") (pin "88") (pinfunction "PD7_88") (pintype "bidirectional"))
    )
    (net (code "46") (name "Net-(U1B-PD9)") (class "Default")
      (node (ref "TP13") (pin "TP") (pinfunction "TP_TP") (pintype "input"))
      (node (ref "U1") (pin "56") (pinfunction "PD9_56") (pintype "bidirectional"))
    )
    (net (code "47") (name "Net-(U1B-PD10)") (class "Default")
      (node (ref "TP10") (pin "TP") (pinfunction "TP_TP") (pintype "input"))
      (node (ref "U1") (pin "57") (pinfunction "PD10_57") (pintype "bidirectional"))
    )
    (net (code "48") (name "Net-(U1B-PD11)") (class "Default")
      (node (ref "TP22") (pin "TP") (pinfunction "TP_TP") (pintype "input"))
      (node (ref "U1") (pin "58") (pinfunction "PD11_58") (pintype "bidirectional"))
    )
    (net (code "49") (name "Net-(U1B-PD12)") (class "Default")
      (node (ref "TP23") (pin "TP") (pinfunction "TP_TP") (pintype "input"))
      (node (ref "U1") (pin "59") (pinfunction "PD12_59") (pintype "bidirectional"))
    )
    (net (code "50") (name "Net-(U1B-PD13)") (class "Default")
      (node (ref "TP12") (pin "TP") (pinfunction "TP_TP") (pintype "input"))
      (node (ref "U1") (pin "60") (pinfunction "PD13_60") (pintype "bidirectional"))
    )
    (net (code "51") (name "Net-(U1B-PD14)") (class "Default")
      (node (ref "TP24") (pin "TP") (pinfunction "TP_TP") (pintype "input"))
      (node (ref "U1") (pin "61") (pinfunction "PD14_61") (pintype "bidirectional"))
    )
    (net (code "52") (name "Net-(U1C-AOUT1{slash}PA4)") (class "Default")
      (node (ref "TP7") (pin "TP") (pinfunction "TP_TP") (pintype "input"))
      (node (ref "U1") (pin "29") (pinfunction "AOUT1/PA4_29") (pintype "bidirectional"))
    )
    (net (code "53") (name "Net-(U1C-CAN1_RX{slash}PD0)") (class "Default")
      (node (ref "TP3") (pin "TP") (pinfunction "TP_TP") (pintype "input"))
      (node (ref "U1") (pin "81") (pinfunction "CAN1_RX/PD0_81") (pintype "bidirectional"))
    )
    (net (code "54") (name "Net-(U1C-CAN1_TX{slash}PD1)") (class "Default")
      (node (ref "TP4") (pin "TP") (pinfunction "TP_TP") (pintype "input"))
      (node (ref "U1") (pin "82") (pinfunction "CAN1_TX/PD1_82") (pintype "bidirectional"))
    )
    (net (code "55") (name "Net-(U1C-NSS4{slash}PE11)") (class "Default")
      (node (ref "TP8") (pin "TP") (pinfunction "TP_TP") (pintype "input"))
      (node (ref "U1") (pin "42") (pinfunction "NSS4/PE11_42") (pintype "bidirectional"))
    )
    (net (code "56") (name "Net-(U1C-SCK4{slash}PE12)") (class "Default")
      (node (ref "TP9") (pin "TP") (pinfunction "TP_TP") (pintype "input"))
      (node (ref "U1") (pin "43") (pinfunction "SCK4/PE12_43") (pintype "bidirectional"))
    )
    (net (code "57") (name "PA5") (class "Default")
      (node (ref "MOD1") (pin "15") (pinfunction "SCK1/LCD/SD_15") (pintype "bidirectional"))
      (node (ref "U1") (pin "30") (pinfunction "SCK1/PA5_30") (pintype "bidirectional"))
      (node (ref "U2") (pin "6") (pinfunction "SCK_6") (pintype "bidirectional"))
    )
    (net (code "58") (name "PA6") (class "Default")
      (node (ref "MOD1") (pin "14") (pinfunction "MISO1/LCD/SD_14") (pintype "bidirectional"))
      (node (ref "U1") (pin "31") (pinfunction "MISO1/PA6_31") (pintype "bidirectional"))
      (node (ref "U2") (pin "2") (pinfunction "SO_2") (pintype "bidirectional"))
    )
    (net (code "59") (name "PA11") (class "Default")
      (node (ref "MOD1") (pin "39") (pinfunction "TGT_CTS_39") (pintype "bidirectional"))
      (node (ref "U1") (pin "70") (pinfunction "PA11_70") (pintype "bidirectional"))
    )
    (net (code "60") (name "PA12") (class "Default")
      (node (ref "MOD1") (pin "38") (pinfunction "TGT_RTS_38") (pintype "bidirectional"))
      (node (ref "U1") (pin "71") (pinfunction "PA12_71") (pintype "bidirectional"))
    )
    (net (code "61") (name "PA15") (class "Default")
      (node (ref "MOD1") (pin "16") (pinfunction "GP0/BUTTON_16") (pintype "bidirectional"))
      (node (ref "U1") (pin "77") (pinfunction "NSS1/PA15_77") (pintype "bidirectional"))
    )
    (net (code "62") (name "PB5") (class "Default")
      (node (ref "MOD1") (pin "13") (pinfunction "MOSI1/LCD/SD_13") (pintype "bidirectional"))
      (node (ref "U1") (pin "91") (pinfunction "MOSI1/PB5_91") (pintype "bidirectional"))
      (node (ref "U2") (pin "5") (pinfunction "SI_5") (pintype "bidirectional"))
    )
    (net (code "63") (name "PB6") (class "Default")
      (node (ref "IC4") (pin "6") (pinfunction "SCL_6") (pintype "bidirectional"))
      (node (ref "MOD1") (pin "12") (pinfunction "SCL1_12") (pintype "bidirectional"))
      (node (ref "R13") (pin "1") (pinfunction "P$1_1") (pintype "passive"))
      (node (ref "U1") (pin "92") (pinfunction "SCL1/PB6_92") (pintype "bidirectional"))
    )
    (net (code "64") (name "PB7") (class "Default")
      (node (ref "IC4") (pin "5") (pinfunction "SDA_5") (pintype "bidirectional"))
      (node (ref "MOD1") (pin "11") (pinfunction "SDA1_11") (pintype "bidirectional"))
      (node (ref "R14") (pin "1") (pinfunction "P$1_1") (pintype "passive"))
      (node (ref "U1") (pin "93") (pinfunction "SDA1/PB7_93") (pintype "bidirectional"))
    )
    (net (code "65") (name "PB8") (class "Default")
      (node (ref "MOD1") (pin "29") (pinfunction "SCL2_29") (pintype "bidirectional"))
      (node (ref "U1") (pin "67") (pinfunction "SCL3/PA8_67") (pintype "bidirectional"))
    )
    (net (code "66") (name "PB14") (class "Default")
      (node (ref "MOD1") (pin "27") (pinfunction "MISO2_27") (pintype "bidirectional"))
      (node (ref "U1") (pin "53") (pinfunction "MISO2/PB14_53") (pintype "bidirectional"))
    )
    (net (code "67") (name "PB15") (class "Default")
      (node (ref "MOD1") (pin "28") (pinfunction "MOSI2_28") (pintype "bidirectional"))
      (node (ref "U1") (pin "54") (pinfunction "MOSI2/PB15_54") (pintype "bidirectional"))
    )
    (net (code "68") (name "PC0") (class "Default")
      (node (ref "MOD1") (pin "18") (pinfunction "AIN0/POT_18") (pintype "bidirectional"))
      (node (ref "TP5") (pin "TP") (pinfunction "TP_TP") (pintype "input"))
      (node (ref "U1") (pin "15") (pinfunction "AIN10/PC0_15") (pintype "bidirectional"))
    )
    (net (code "69") (name "PC9") (class "Default")
      (node (ref "MOD1") (pin "30") (pinfunction "SDA2_30") (pintype "bidirectional"))
      (node (ref "U1") (pin "66") (pinfunction "SDA3/PC9_66") (pintype "bidirectional"))
    )
    (net (code "70") (name "PC10") (class "Default")
      (node (ref "MOD1") (pin "17") (pinfunction "GP1_17") (pintype "bidirectional"))
      (node (ref "U1") (pin "78") (pinfunction "SCK3/PC10_78") (pintype "bidirectional"))
    )
    (net (code "71") (name "PC11") (class "Default")
      (node (ref "MOD1") (pin "19") (pinfunction "AIN1/GROVE_19") (pintype "bidirectional"))
      (node (ref "U1") (pin "79") (pinfunction "MISO3/PC11_79") (pintype "bidirectional"))
    )
    (net (code "72") (name "PC12") (class "Default")
      (node (ref "MOD1") (pin "20") (pinfunction "AIN2/GROVE_20") (pintype "bidirectional"))
      (node (ref "U1") (pin "80") (pinfunction "MOSI3/PC12_80") (pintype "bidirectional"))
    )
    (net (code "73") (name "PD3") (class "Default")
      (node (ref "MOD1") (pin "26") (pinfunction "SCK2_26") (pintype "bidirectional"))
      (node (ref "U1") (pin "84") (pinfunction "SCK2/PD3_84") (pintype "bidirectional"))
    )
    (net (code "74") (name "PE0") (class "Default")
      (node (ref "MOD1") (pin "31") (pinfunction "RX2_31") (pintype "bidirectional"))
      (node (ref "U1") (pin "97") (pinfunction "RX8/PE0_97") (pintype "bidirectional"))
    )
    (net (code "75") (name "PE1") (class "Default")
      (node (ref "MOD1") (pin "32") (pinfunction "TX2_32") (pintype "bidirectional"))
      (node (ref "U1") (pin "98") (pinfunction "TX8/PE1_98") (pintype "bidirectional"))
    )
    (net (code "76") (name "PE2") (class "Default")
      (node (ref "MOD1") (pin "21") (pinfunction "PWM0/RED-LED_21") (pintype "bidirectional"))
      (node (ref "U1") (pin "1") (pinfunction "PE2_1") (pintype "bidirectional"))
    )
    (net (code "77") (name "PE3") (class "Default")
      (node (ref "MOD1") (pin "22") (pinfunction "PWM1/BLUE-LED_22") (pintype "bidirectional"))
      (node (ref "U1") (pin "2") (pinfunction "PE3_2") (pintype "bidirectional"))
    )
    (net (code "78") (name "PE4") (class "Default")
      (node (ref "MOD1") (pin "23") (pinfunction "PWM2/GREEN-LED_23") (pintype "bidirectional"))
      (node (ref "U1") (pin "3") (pinfunction "PE4_3") (pintype "bidirectional"))
    )
    (net (code "79") (name "PE5") (class "Default")
      (node (ref "MOD1") (pin "24") (pinfunction "GP2/SDCARD-~{CS}/GROVE_24") (pintype "bidirectional"))
      (node (ref "U1") (pin "4") (pinfunction "MISO4/PE5_4") (pintype "bidirectional"))
    )
    (net (code "80") (name "PE6") (class "Default")
      (node (ref "MOD1") (pin "25") (pinfunction "GP3/GROVE_25") (pintype "bidirectional"))
      (node (ref "U1") (pin "5") (pinfunction "MOSI4/PE6_5") (pintype "bidirectional"))
    )
    (net (code "81") (name "PE7") (class "Default")
      (node (ref "MOD1") (pin "10") (pinfunction "RX1_10") (pintype "bidirectional"))
      (node (ref "U1") (pin "38") (pinfunction "RX7/PE7_38") (pintype "bidirectional"))
    )
    (net (code "82") (name "PE8") (class "Default")
      (node (ref "MOD1") (pin "9") (pinfunction "TX1_9") (pintype "bidirectional"))
      (node (ref "U1") (pin "39") (pinfunction "TX7/PE8_39") (pintype "bidirectional"))
    )
    (net (code "83") (name "PE9") (class "Default")
      (node (ref "MOD1") (pin "33") (pinfunction "GP4_33") (pintype "bidirectional"))
      (node (ref "U1") (pin "40") (pinfunction "PE9_40") (pintype "bidirectional"))
    )
    (net (code "84") (name "PE10") (class "Default")
      (node (ref "MOD1") (pin "34") (pinfunction "GP5/LCD-A0_34") (pintype "bidirectional"))
      (node (ref "U1") (pin "41") (pinfunction "PE10_41") (pintype "bidirectional"))
    )
    (net (code "85") (name "PE13") (class "Default")
      (node (ref "MOD1") (pin "35") (pinfunction "GP6/LCD-RESET_35") (pintype "bidirectional"))
      (node (ref "U1") (pin "44") (pinfunction "PE13_44") (pintype "bidirectional"))
    )
    (net (code "86") (name "PE14") (class "Default")
      (node (ref "MOD1") (pin "36") (pinfunction "GP7/LCD~{CS}_36") (pintype "bidirectional"))
      (node (ref "U1") (pin "45") (pinfunction "PE14_45") (pintype "bidirectional"))
    )
    (net (code "87") (name "PE15") (class "Default")
      (node (ref "MOD1") (pin "37") (pinfunction "GP8_37") (pintype "bidirectional"))
      (node (ref "U1") (pin "46") (pinfunction "PE15_46") (pintype "bidirectional"))
    )
    (net (code "88") (name "RD+") (class "Default")
      (node (ref "CON1") (pin "4") (pinfunction "4_4") (pintype "passive"))
      (node (ref "IC1") (pin "14") (pinfunction "RD+_14") (pintype "bidirectional"))
      (node (ref "R4") (pin "1") (pinfunction "P$1_1") (pintype "passive"))
    )
    (net (code "89") (name "RD-") (class "Default")
      (node (ref "CON1") (pin "6") (pinfunction "6_6") (pintype "passive"))
      (node (ref "IC1") (pin "13") (pinfunction "RD-_13") (pintype "bidirectional"))
      (node (ref "R5") (pin "1") (pinfunction "P$1_1") (pintype "passive"))
    )
    (net (code "90") (name "SD_CS") (class "Default")
      (node (ref "U1") (pin "83") (pinfunction "PD2_83") (pintype "bidirectional"))
      (node (ref "U2") (pin "1") (pinfunction "~{CS}_1") (pintype "bidirectional"))
    )
    (net (code "91") (name "TD+") (class "Default")
      (node (ref "CON1") (pin "1") (pinfunction "1_1") (pintype "passive"))
      (node (ref "IC1") (pin "17") (pinfunction "TD+_17") (pintype "bidirectional"))
      (node (ref "R2") (pin "1") (pinfunction "P$1_1") (pintype "passive"))
    )
    (net (code "92") (name "TD-") (class "Default")
      (node (ref "CON1") (pin "3") (pinfunction "3_3") (pintype "passive"))
      (node (ref "IC1") (pin "16") (pinfunction "TD-_16") (pintype "bidirectional"))
      (node (ref "R3") (pin "1") (pinfunction "P$1_1") (pintype "passive"))
    )
    (net (code "93") (name "TGT_NRST") (class "Default")
      (node (ref "CON2") (pin "3") (pinfunction "NRESET_3") (pintype "passive"))
      (node (ref "IC1") (pin "29") (pinfunction "RESET_N_29") (pintype "bidirectional"))
      (node (ref "MOD1") (pin "6") (pinfunction "NRESET_6") (pintype "bidirectional"))
      (node (ref "U1") (pin "14") (pinfunction "NRST_14") (pintype "bidirectional"))
    )
    (net (code "94") (name "TGT_RX") (class "Default")
      (node (ref "MOD1") (pin "8") (pinfunction "TGT_RX_8") (pintype "bidirectional"))
      (node (ref "U1") (pin "68") (pinfunction "TGT_RX/PA10_68") (pintype "bidirectional"))
    )
    (net (code "95") (name "TGT_SWCLK") (class "Default")
      (node (ref "CON2") (pin "4") (pinfunction "SWCLK/TCLK_4") (pintype "passive"))
      (node (ref "MOD1") (pin "5") (pinfunction "SWCLK_5") (pintype "bidirectional"))
      (node (ref "U1") (pin "76") (pinfunction "SWCLK/PA14_76") (pintype "bidirectional"))
    )
    (net (code "96") (name "TGT_SWDIO") (class "Default")
      (node (ref "CON2") (pin "2") (pinfunction "SWDIO/TMS_2") (pintype "passive"))
      (node (ref "MOD1") (pin "4") (pinfunction "SWDIO_4") (pintype "bidirectional"))
      (node (ref "U1") (pin "72") (pinfunction "SWDIO/PA13_72") (pintype "bidirectional"))
    )
    (net (code "97") (name "TGT_SWO") (class "Default")
      (node (ref "CON2") (pin "6") (pinfunction "SWO/TDO_6") (pintype "passive"))
      (node (ref "U1") (pin "89") (pinfunction "SWO/PB3_89") (pintype "bidirectional"))
    )
    (net (code "98") (name "TGT_TX") (class "Default")
      (node (ref "MOD1") (pin "7") (pinfunction "TGT_TX_7") (pintype "bidirectional"))
      (node (ref "U1") (pin "69") (pinfunction "TGT_TX/PA9_69") (pintype "bidirectional"))
    )
    (net (code "99") (name "unconnected-(CON1-Pad7)") (class "Default")
      (node (ref "CON1") (pin "7") (pinfunction "7_7") (pintype "passive"))
    )
    (net (code "100") (name "unconnected-(IC1-25MHZ_OUT-Pad25)") (class "Default")
      (node (ref "IC1") (pin "25") (pinfunction "25MHZ_OUT_25") (pintype "bidirectional"))
    )
    (net (code "101") (name "unconnected-(IC1-NC-Pad8)") (class "Default")
      (node (ref "IC1") (pin "8") (pinfunction "NC_8") (pintype "bidirectional"))
    )
    (net (code "102") (name "unconnected-(IC1-NC-Pad9)") (class "Default")
      (node (ref "IC1") (pin "9") (pinfunction "NC_9") (pintype "bidirectional"))
    )
    (net (code "103") (name "unconnected-(IC1-NC-Pad10)") (class "Default")
      (node (ref "IC1") (pin "10") (pinfunction "NC_10") (pintype "bidirectional"))
    )
    (net (code "104") (name "unconnected-(IC1-NC-Pad11)") (class "Default")
      (node (ref "IC1") (pin "11") (pinfunction "NC_11") (pintype "bidirectional"))
    )
    (net (code "105") (name "unconnected-(IC1-NC-Pad12)") (class "Default")
      (node (ref "IC1") (pin "12") (pinfunction "NC_12") (pintype "bidirectional"))
    )
    (net (code "106") (name "unconnected-(IC4-NC1-Pad1)") (class "Default")
      (node (ref "IC4") (pin "1") (pinfunction "NC1_1") (pintype "bidirectional"))
    )
    (net (code "107") (name "unconnected-(IC4-NC2-Pad2)") (class "Default")
      (node (ref "IC4") (pin "2") (pinfunction "NC2_2") (pintype "bidirectional"))
    )
    (net (code "108") (name "unconnected-(IC4-NC3-Pad3)") (class "Default")
      (node (ref "IC4") (pin "3") (pinfunction "NC3_3") (pintype "bidirectional"))
    )
    (net (code "109") (name "unconnected-(IC4-NC7-Pad7)") (class "Default")
      (node (ref "IC4") (pin "7") (pinfunction "NC7_7") (pintype "bidirectional"))
    )
    (net (code "110") (name "unconnected-(MOD1-5V-USB-Pad3)") (class "Default")
      (node (ref "MOD1") (pin "3") (pinfunction "5V-USB_3") (pintype "bidirectional"))
    )
    (net (code "111") (name "unconnected-(U1B-PB2-Pad37)") (class "Default")
      (node (ref "U1") (pin "37") (pinfunction "PB2_37") (pintype "bidirectional"))
    )
    (net (code "112") (name "unconnected-(U1B-PC13-Pad7)") (class "Default")
      (node (ref "U1") (pin "7") (pinfunction "PC13_7") (pintype "bidirectional"))
    )
    (net (code "113") (name "unconnected-(U1B-PD15-Pad62)") (class "Default")
      (node (ref "U1") (pin "62") (pinfunction "PD15_62") (pintype "bidirectional"))
    )
    (net (code "114") (name "unconnected-(U1C-NSS2{slash}SDA1{slash}PB9-Pad96)") (class "Default")
      (node (ref "U1") (pin "96") (pinfunction "NSS2/SDA1/PB9_96") (pintype "bidirectional"))
    )
  )
)
